# Servorino_FT230X_brick_headers.net
KiCad netlist of a schematic drawn in EAGLE
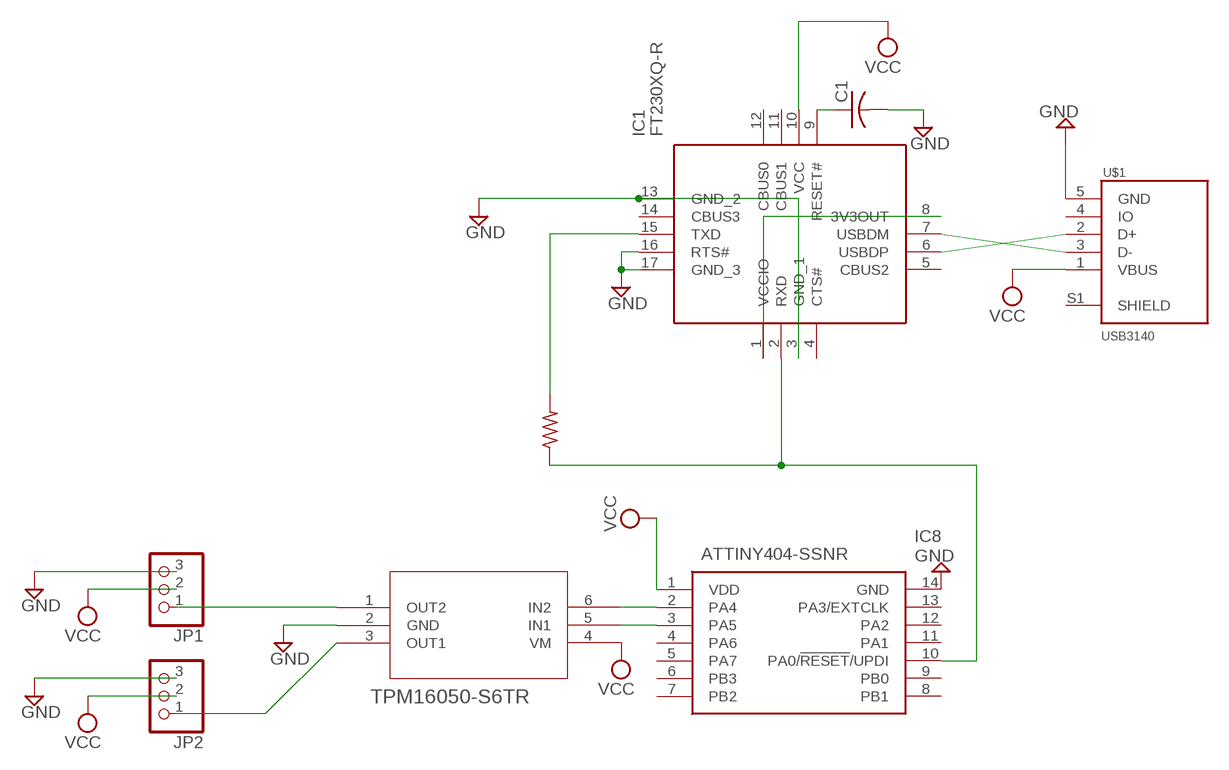
[diagram p0: schematic, sheet 1]

(export (version "E")
  (design (tool "Eeschema 10.0.6"))
  (components
    (comp (ref "C1")
      (value "C-USC0603")
      (footprint "eagle-import:C0603")
      (libsource (lib "eagle-import") (part "C-USC0603"))
    )
    (comp (ref "IC1")
      (value "FT230XQ-R")
      (footprint "eagle-import:QFN65P400X400X80-17N")
      (fields (field (name "MOUSER_PART_NUMBER") "895-FT230XQ-R"))
      (libsource (lib "eagle-import") (part "FT230XQ-R"))
    )
    (comp (ref "IC8")
      (value "ATTINY404-SSNR")
      (footprint "eagle-import:SOIC127P600X175-14N")
      (fields (field (name "MOUSER_PART_NUMBER") "556-ATTINY404-SSNR"))
      (libsource (lib "eagle-import") (part "ATTINY404-SSNR"))
    )
    (comp (ref "JP1")
      (value "PINHD-1X3")
      (footprint "eagle-import:1X03")
      (libsource (lib "eagle-import") (part "PINHD-1X3"))
    )
    (comp (ref "JP2")
      (value "PINHD-1X3")
      (footprint "eagle-import:1X03")
      (libsource (lib "eagle-import") (part "PINHD-1X3"))
    )
    (comp (ref "R6")
      (value "470")
      (footprint "eagle-import:R0805")
      (libsource (lib "eagle-import") (part "R-US_R0805"))
    )
    (comp (ref "U$1")
      (value "USB3140")
      (footprint "eagle-import:USB3140-30-0170-0-C")
      (libsource (lib "eagle-import") (part "USB3140"))
    )
    (comp (ref "U1")
      (value "TPM16050-S6TR")
      (footprint "eagle-import:SOT23-6_TPK")
      (fields (field (name "COPYRIGHT") "Copyright (C) 2025 Ultra Librarian. All rights reserved."))
      (libsource (lib "eagle-import") (part "TPM16050-S6TR"))
    )
  )
  (nets
    (net (code "1") (name "GND") (class "Default")
      (node (ref "C1") (pin "2") (pinfunction "2_2") (pintype "passive"))
      (node (ref "IC1") (pin "13") (pinfunction "GND_2_13") (pintype "bidirectional"))
      (node (ref "IC1") (pin "16") (pinfunction "RTS#_16") (pintype "bidirectional"))
      (node (ref "IC1") (pin "17") (pinfunction "GND_3_17") (pintype "bidirectional"))
      (node (ref "IC1") (pin "3") (pinfunction "GND_1_3") (pintype "bidirectional"))
      (node (ref "IC8") (pin "14") (pinfunction "GND_14") (pintype "bidirectional"))
      (node (ref "JP1") (pin "3") (pinfunction "3_3") (pintype "passive"))
      (node (ref "JP2") (pin "3") (pinfunction "3_3") (pintype "passive"))
      (node (ref "U$1") (pin "5") (pinfunction "GND_5") (pintype "passive"))
      (node (ref "U1") (pin "2") (pinfunction "GND_2") (pintype "passive"))
    )
    (net (code "2") (name "Net-(IC1-3V3OUT)") (class "Default")
      (node (ref "IC1") (pin "1") (pinfunction "VCCIO_1") (pintype "bidirectional"))
      (node (ref "IC1") (pin "8") (pinfunction "3V3OUT_8") (pintype "bidirectional"))
    )
    (net (code "3") (name "Net-(IC1-RESET#)") (class "Default")
      (node (ref "C1") (pin "1") (pinfunction "1_1") (pintype "passive"))
      (node (ref "IC1") (pin "9") (pinfunction "RESET#_9") (pintype "bidirectional"))
    )
    (net (code "4") (name "Net-(IC1-RXD)") (class "Default")
      (node (ref "IC1") (pin "2") (pinfunction "RXD_2") (pintype "bidirectional"))
      (node (ref "IC8") (pin "10") (pinfunction "PA0/~{RESET}/UPDI_10") (pintype "bidirectional"))
      (node (ref "R6") (pin "1") (pinfunction "1_1") (pintype "passive"))
    )
    (net (code "5") (name "Net-(IC1-TXD)") (class "Default")
      (node (ref "IC1") (pin "15") (pinfunction "TXD_15") (pintype "bidirectional"))
      (node (ref "R6") (pin "2") (pinfunction "2_2") (pintype "passive"))
    )
    (net (code "6") (name "Net-(IC1-USBDM)") (class "Default")
      (node (ref "IC1") (pin "7") (pinfunction "USBDM_7") (pintype "bidirectional"))
      (node (ref "U$1") (pin "3") (pinfunction "D-_3") (pintype "passive"))
    )
    (net (code "7") (name "Net-(IC1-USBDP)") (class "Default")
      (node (ref "IC1") (pin "6") (pinfunction "USBDP_6") (pintype "bidirectional"))
      (node (ref "U$1") (pin "2") (pinfunction "D+_2") (pintype "passive"))
    )
    (net (code "8") (name "Net-(IC8-PA4)") (class "Default")
      (node (ref "IC8") (pin "2") (pinfunction "PA4_2") (pintype "bidirectional"))
      (node (ref "U1") (pin "6") (pinfunction "IN2_6") (pintype "input"))
    )
    (net (code "9") (name "Net-(IC8-PA5)") (class "Default")
      (node (ref "IC8") (pin "3") (pinfunction "PA5_3") (pintype "bidirectional"))
      (node (ref "U1") (pin "5") (pinfunction "IN1_5") (pintype "input"))
    )
    (net (code "10") (name "Net-(U1-OUT1)") (class "Default")
      (node (ref "JP2") (pin "1") (pinfunction "1_1") (pintype "passive"))
      (node (ref "U1") (pin "3") (pinfunction "OUT1_3") (pintype "output"))
    )
    (net (code "11") (name "Net-(U1-OUT2)") (class "Default")
      (node (ref "JP1") (pin "1") (pinfunction "1_1") (pintype "passive"))
      (node (ref "U1") (pin "1") (pinfunction "OUT2_1") (pintype "output"))
    )
    (net (code "12") (name "VCC") (class "Default")
      (node (ref "IC1") (pin "10") (pinfunction "VCC_10") (pintype "bidirectional"))
      (node (ref "IC8") (pin "1") (pinfunction "VDD_1") (pintype "bidirectional"))
      (node (ref "JP1") (pin "2") (pinfunction "2_2") (pintype "passive"))
      (node (ref "JP2") (pin "2") (pinfunction "2_2") (pintype "passive"))
      (node (ref "U$1") (pin "1") (pinfunction "VBUS_1") (pintype "passive"))
      (node (ref "U1") (pin "4") (pinfunction "VM_4") (pintype "power_in"))
    )
    (net (code "13") (name "unconnected-(IC1-CBUS0-Pad12)") (class "Default")
      (node (ref "IC1") (pin "12") (pinfunction "CBUS0_12") (pintype "bidirectional"))
    )
    (net (code "14") (name "unconnected-(IC1-CBUS1-Pad11)") (class "Default")
      (node (ref "IC1") (pin "11") (pinfunction "CBUS1_11") (pintype "bidirectional"))
    )
    (net (code "15") (name "unconnected-(IC1-CBUS2-Pad5)") (class "Default")
      (node (ref "IC1") (pin "5") (pinfunction "CBUS2_5") (pintype "bidirectional"))
    )
    (net (code "16") (name "unconnected-(IC1-CBUS3-Pad14)") (class "Default")
      (node (ref "IC1") (pin "14") (pinfunction "CBUS3_14") (pintype "bidirectional"))
    )
    (net (code "17") (name "unconnected-(IC1-CTS#-Pad4)") (class "Default")
      (node (ref "IC1") (pin "4") (pinfunction "CTS#_4") (pintype "bidirectional"))
    )
    (net (code "18") (name "unconnected-(IC8-PA1-Pad11)") (class "Default")
      (node (ref "IC8") (pin "11") (pinfunction "PA1_11") (pintype "bidirectional"))
    )
    (net (code "19") (name "unconnected-(IC8-PA2-Pad12)") (class "Default")
      (node (ref "IC8") (pin "12") (pinfunction "PA2_12") (pintype "bidirectional"))
    )
    (net (code "20") (name "unconnected-(IC8-PA3{slash}EXTCLK-Pad13)") (class "Default")
      (node (ref "IC8") (pin "13") (pinfunction "PA3/EXTCLK_13") (pintype "bidirectional"))
    )
    (net (code "21") (name "unconnected-(IC8-PA6-Pad4)") (class "Default")
      (node (ref "IC8") (pin "4") (pinfunction "PA6_4") (pintype "bidirectional"))
    )
    (net (code "22") (name "unconnected-(IC8-PA7-Pad5)") (class "Default")
      (node (ref "IC8") (pin "5") (pinfunction "PA7_5") (pintype "bidirectional"))
    )
    (net (code "23") (name "unconnected-(IC8-PB0-Pad9)") (class "Default")
      (node (ref "IC8") (pin "9") (pinfunction "PB0_9") (pintype "bidirectional"))
    )
    (net (code "24") (name "unconnected-(IC8-PB1-Pad8)") (class "Default")
      (node (ref "IC8") (pin "8") (pinfunction "PB1_8") (pintype "bidirectional"))
    )
    (net (code "25") (name "unconnected-(IC8-PB2-Pad7)") (class "Default")
      (node (ref "IC8") (pin "7") (pinfunction "PB2_7") (pintype "bidirectional"))
    )
    (net (code "26") (name "unconnected-(IC8-PB3-Pad6)") (class "Default")
      (node (ref "IC8") (pin "6") (pinfunction "PB3_6") (pintype "bidirectional"))
    )
    (net (code "27") (name "unconnected-(U$1-IO-Pad4)") (class "Default")
      (node (ref "U$1") (pin "4") (pinfunction "IO_4") (pintype "passive"))
    )
    (net (code "28") (name "unconnected-(U$1-SHIELD-PadS1)") (class "Default")
      (node (ref "U$1") (pin "S1") (pinfunction "SHIELD_S1") (pintype "passive"))
    )
  )
)
